# IRsensor.net
KiCad netlist of a schematic drawn in EAGLE
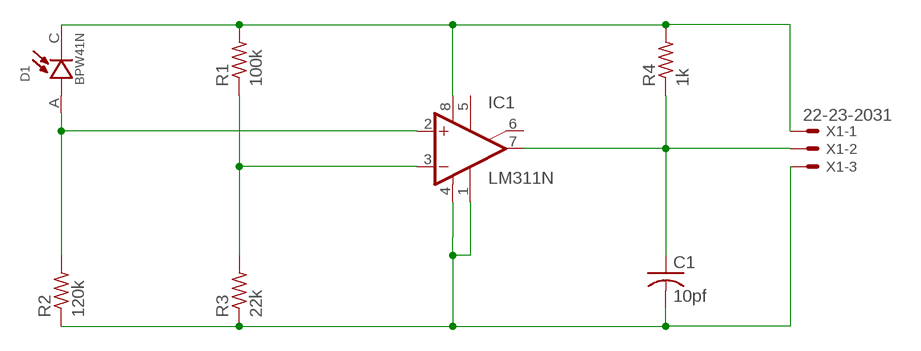
[diagram p0: schematic, sheet 1]

(export (version "E")
  (design (tool "Eeschema 10.0.6"))
  (components
    (comp (ref "C1")
      (value "10pf")
      (footprint "eagle-import:C025-024X044")
      (libsource (lib "eagle-import") (part "C-US025-024X044"))
    )
    (comp (ref "D1")
      (value "BPW41N")
      (footprint "eagle-import:DIO_BPW41N")
      (fields (field (name "MF") "Vishay Semiconductor Opto Division"))
      (libsource (lib "eagle-import") (part "BPW41N"))
    )
    (comp (ref "IC1")
      (value "LM311N")
      (footprint "eagle-import:DIL08")
      (libsource (lib "eagle-import") (part "LM311N"))
    )
    (comp (ref "R1")
      (value "100k")
      (footprint "eagle-import:0204_5")
      (libsource (lib "eagle-import") (part "R-US_0204/5"))
    )
    (comp (ref "R2")
      (value "120k")
      (footprint "eagle-import:0204_5")
      (libsource (lib "eagle-import") (part "R-US_0204/5"))
    )
    (comp (ref "R3")
      (value "22k")
      (footprint "eagle-import:0204_5")
      (libsource (lib "eagle-import") (part "R-US_0204/5"))
    )
    (comp (ref "R4")
      (value "1k")
      (footprint "eagle-import:0204_5")
      (libsource (lib "eagle-import") (part "R-US_0204/5"))
    )
    (comp (ref "X1")
      (value "22-23-2031")
      (footprint "eagle-import:22-23-2031")
      (fields (field (name "MF") "MOLEX"))
      (libsource (lib "eagle-import") (part "22-23-2031"))
    )
  )
  (nets
    (net (code "1") (name "Net-(IC1-+IN)") (class "Default")
      (node (ref "D1") (pin "A") (pinfunction "A_A") (pintype "passive"))
      (node (ref "IC1") (pin "2") (pinfunction "+IN_2") (pintype "input"))
      (node (ref "R2") (pin "2") (pinfunction "2_2") (pintype "passive"))
    )
    (net (code "2") (name "Net-(IC1--IN)") (class "Default")
      (node (ref "IC1") (pin "3") (pinfunction "-IN_3") (pintype "input"))
      (node (ref "R1") (pin "1") (pinfunction "1_1") (pintype "passive"))
      (node (ref "R3") (pin "2") (pinfunction "2_2") (pintype "passive"))
    )
    (net (code "3") (name "Net-(IC1-GND)") (class "Default")
      (node (ref "C1") (pin "2") (pinfunction "2_2") (pintype "passive"))
      (node (ref "IC1") (pin "1") (pinfunction "GND_1") (pintype "passive"))
      (node (ref "IC1") (pin "4") (pinfunction "V-_4") (pintype "power_in"))
      (node (ref "R2") (pin "1") (pinfunction "1_1") (pintype "passive"))
      (node (ref "R3") (pin "1") (pinfunction "1_1") (pintype "passive"))
      (node (ref "X1") (pin "3") (pinfunction "S_3") (pintype "passive"))
    )
    (net (code "4") (name "Net-(IC1-OUT)") (class "Default")
      (node (ref "C1") (pin "1") (pinfunction "1_1") (pintype "passive"))
      (node (ref "IC1") (pin "7") (pinfunction "OUT_7") (pintype "output"))
      (node (ref "R4") (pin "1") (pinfunction "1_1") (pintype "passive"))
      (node (ref "X1") (pin "2") (pinfunction "S_2") (pintype "passive"))
    )
    (net (code "5") (name "Net-(IC1-V+)") (class "Default")
      (node (ref "D1") (pin "C") (pinfunction "C_C") (pintype "passive"))
      (node (ref "IC1") (pin "8") (pinfunction "V+_8") (pintype "power_in"))
      (node (ref "R1") (pin "2") (pinfunction "2_2") (pintype "passive"))
      (node (ref "R4") (pin "2") (pinfunction "2_2") (pintype "passive"))
      (node (ref "X1") (pin "1") (pinfunction "S_1") (pintype "passive"))
    )
    (net (code "6") (name "unconnected-(IC1-ON-Pad5)") (class "Default")
      (node (ref "IC1") (pin "5") (pinfunction "ON_5") (pintype "passive"))
    )
    (net (code "7") (name "unconnected-(IC1-ON{slash}STR-Pad6)") (class "Default")
      (node (ref "IC1") (pin "6") (pinfunction "ON/STR_6") (pintype "passive"))
    )
  )
)
